# schematics.net
KiCad netlist of a schematic drawn in EasyEDA
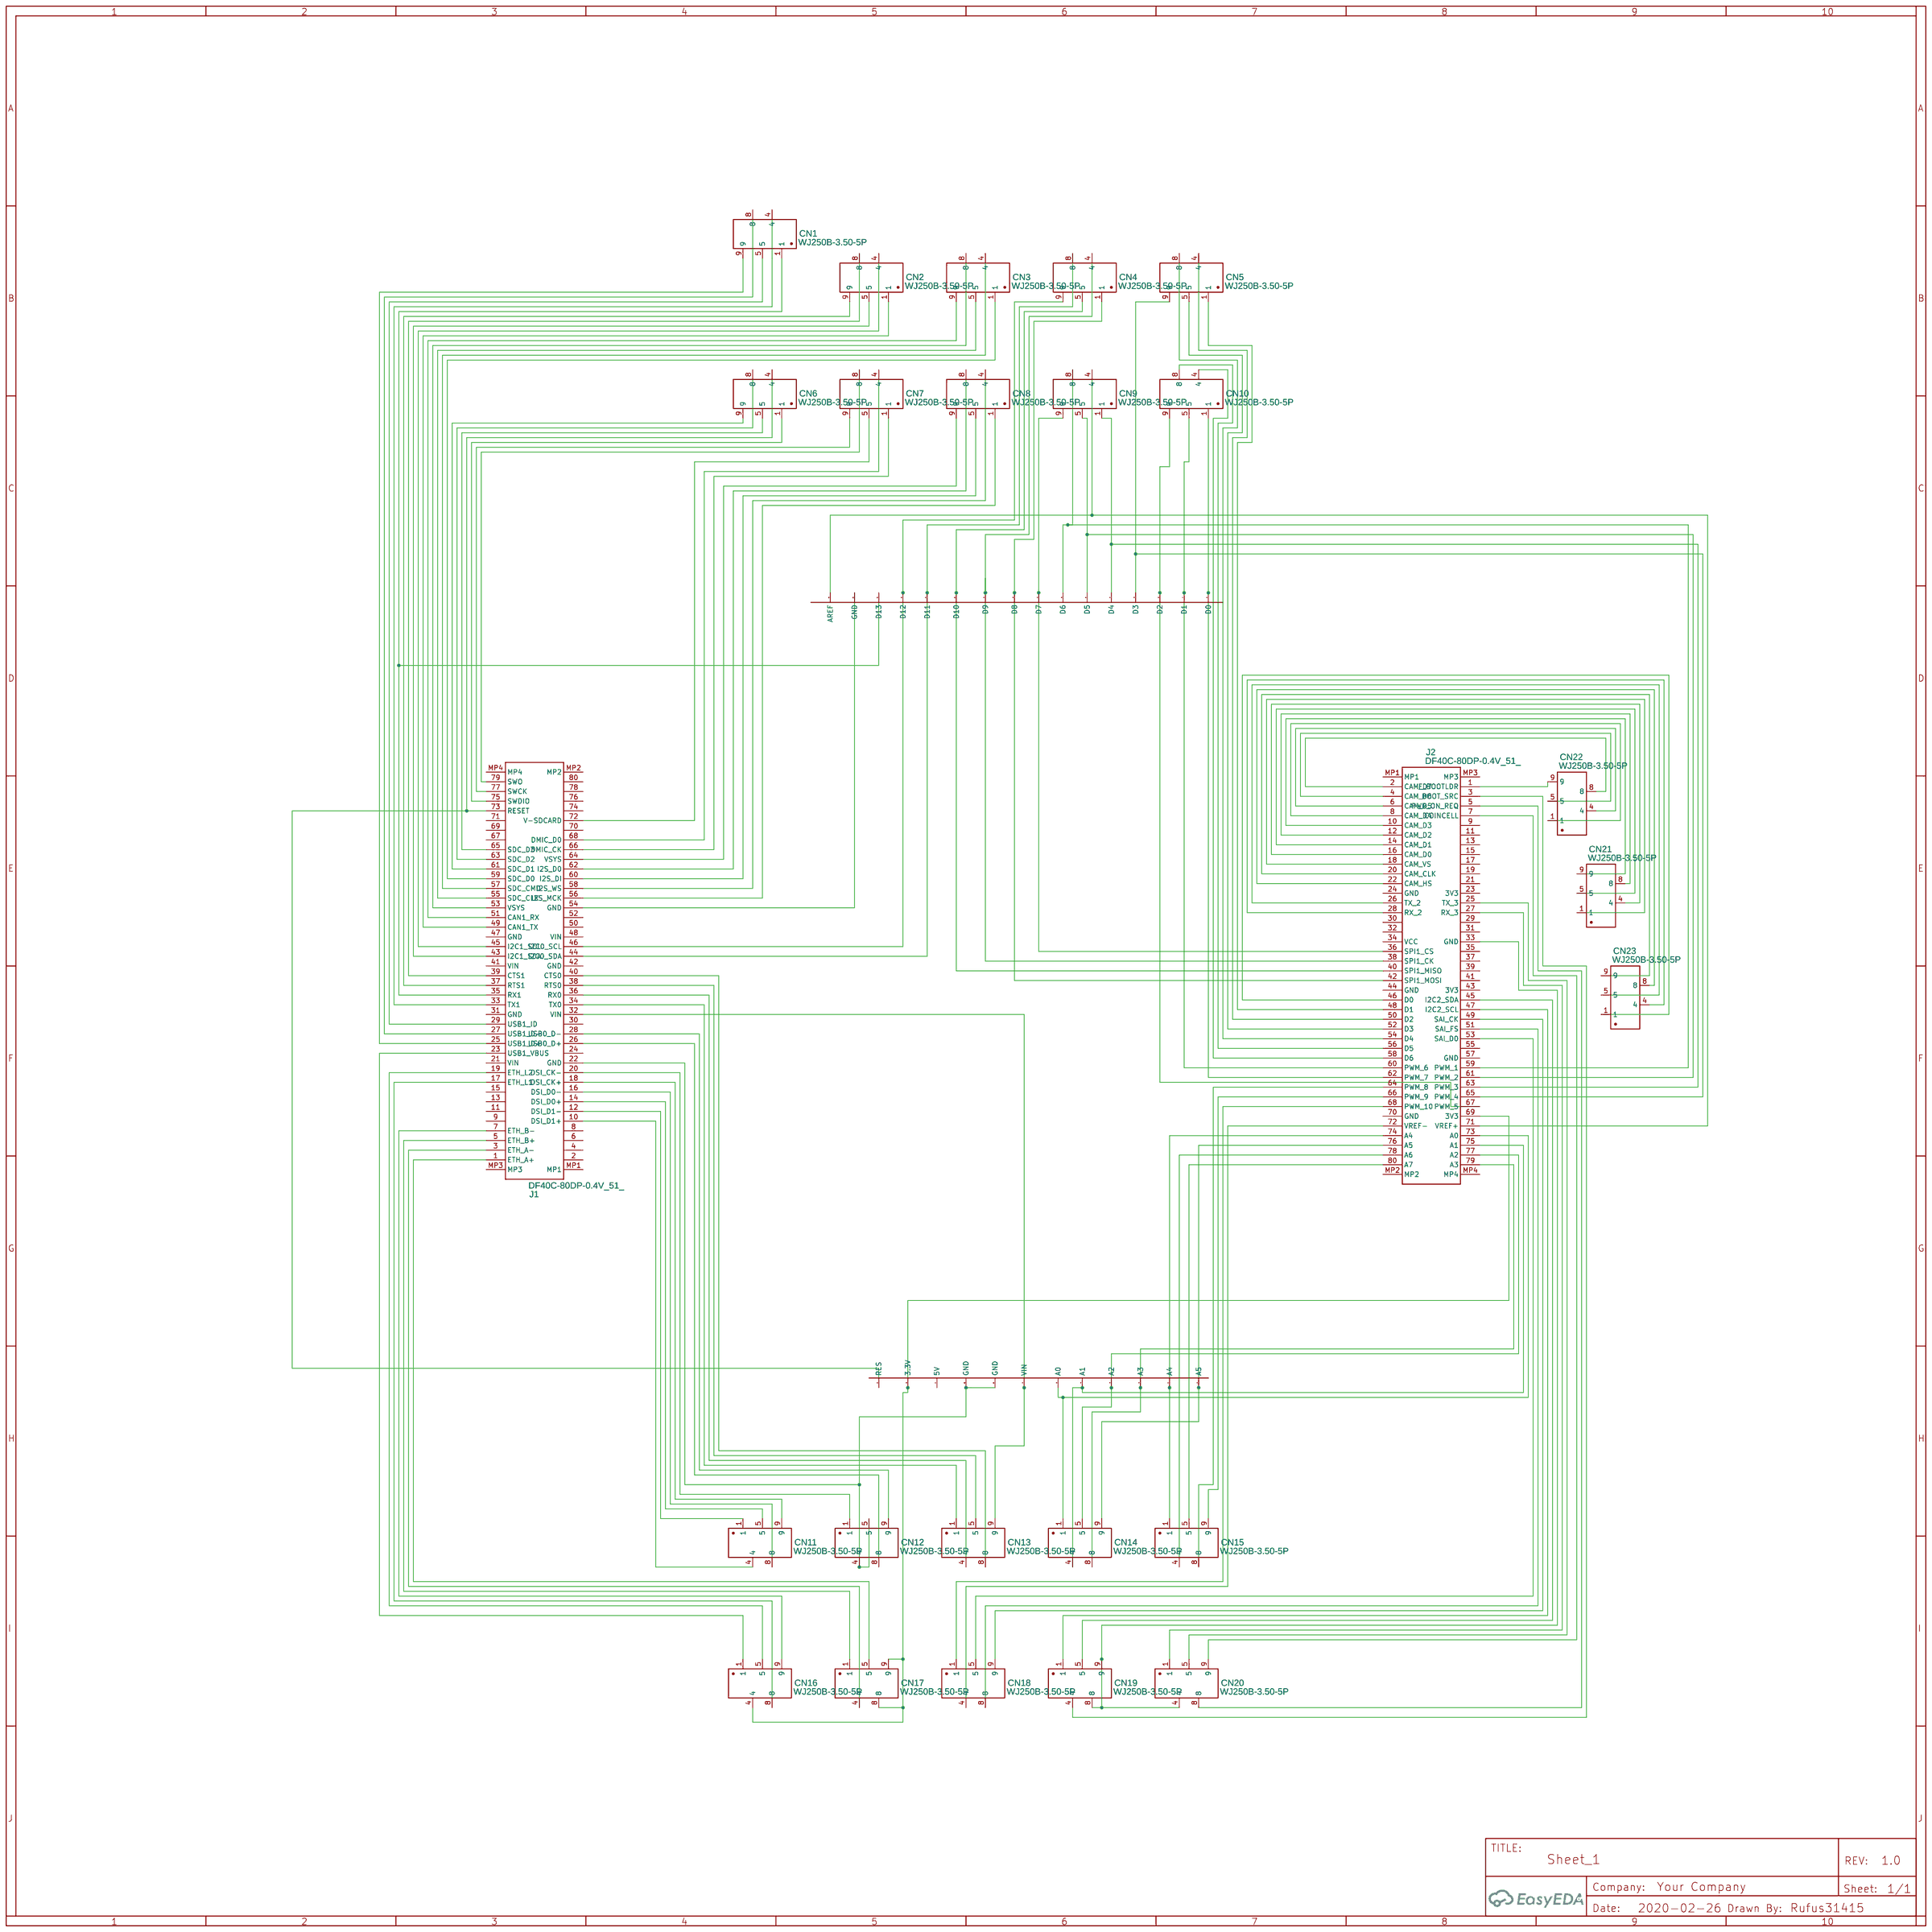
[diagram p0: schematic sheet]

(export (version "E")
  (design (tool "Eeschema 10.0.6"))
  (components
    (comp (ref "CN1")
      (value "WJ250B-3.50-5P")
      (fields (field (name "BOM_Supplier Part") "C8453"))
      (libsource (lib "") (part "WJ250B-3.50-5P_1"))
    )
    (comp (ref "CN2")
      (value "WJ250B-3.50-5P")
      (fields (field (name "BOM_Supplier Part") "C8453"))
      (libsource (lib "") (part "WJ250B-3.50-5P_1"))
    )
    (comp (ref "CN3")
      (value "WJ250B-3.50-5P")
      (fields (field (name "BOM_Supplier Part") "C8453"))
      (libsource (lib "") (part "WJ250B-3.50-5P_1"))
    )
    (comp (ref "CN4")
      (value "WJ250B-3.50-5P")
      (fields (field (name "BOM_Supplier Part") "C8453"))
      (libsource (lib "") (part "WJ250B-3.50-5P_1"))
    )
    (comp (ref "CN5")
      (value "WJ250B-3.50-5P")
      (fields (field (name "BOM_Supplier Part") "C8453"))
      (libsource (lib "") (part "WJ250B-3.50-5P_1"))
    )
    (comp (ref "CN6")
      (value "WJ250B-3.50-5P")
      (fields (field (name "BOM_Supplier Part") "C8453"))
      (libsource (lib "") (part "WJ250B-3.50-5P_1"))
    )
    (comp (ref "CN7")
      (value "WJ250B-3.50-5P")
      (fields (field (name "BOM_Supplier Part") "C8453"))
      (libsource (lib "") (part "WJ250B-3.50-5P_1"))
    )
    (comp (ref "CN8")
      (value "WJ250B-3.50-5P")
      (fields (field (name "BOM_Supplier Part") "C8453"))
      (libsource (lib "") (part "WJ250B-3.50-5P_1"))
    )
    (comp (ref "CN9")
      (value "WJ250B-3.50-5P")
      (fields (field (name "BOM_Supplier Part") "C8453"))
      (libsource (lib "") (part "WJ250B-3.50-5P_1"))
    )
    (comp (ref "CN10")
      (value "WJ250B-3.50-5P")
      (fields (field (name "BOM_Supplier Part") "C8453"))
      (libsource (lib "") (part "WJ250B-3.50-5P_1"))
    )
    (comp (ref "CN11")
      (value "WJ250B-3.50-5P")
      (fields (field (name "BOM_Supplier Part") "C8453"))
      (libsource (lib "") (part "WJ250B-3.50-5P"))
    )
    (comp (ref "CN12")
      (value "WJ250B-3.50-5P")
      (fields (field (name "BOM_Supplier Part") "C8453"))
      (libsource (lib "") (part "WJ250B-3.50-5P"))
    )
    (comp (ref "CN13")
      (value "WJ250B-3.50-5P")
      (fields (field (name "BOM_Supplier Part") "C8453"))
      (libsource (lib "") (part "WJ250B-3.50-5P"))
    )
    (comp (ref "CN14")
      (value "WJ250B-3.50-5P")
      (fields (field (name "BOM_Supplier Part") "C8453"))
      (libsource (lib "") (part "WJ250B-3.50-5P"))
    )
    (comp (ref "CN15")
      (value "WJ250B-3.50-5P")
      (fields (field (name "BOM_Supplier Part") "C8453"))
      (libsource (lib "") (part "WJ250B-3.50-5P"))
    )
    (comp (ref "CN16")
      (value "WJ250B-3.50-5P")
      (fields (field (name "BOM_Supplier Part") "C8453"))
      (libsource (lib "") (part "WJ250B-3.50-5P"))
    )
    (comp (ref "CN17")
      (value "WJ250B-3.50-5P")
      (fields (field (name "BOM_Supplier Part") "C8453"))
      (libsource (lib "") (part "WJ250B-3.50-5P"))
    )
    (comp (ref "CN18")
      (value "WJ250B-3.50-5P")
      (fields (field (name "BOM_Supplier Part") "C8453"))
      (libsource (lib "") (part "WJ250B-3.50-5P"))
    )
    (comp (ref "CN19")
      (value "WJ250B-3.50-5P")
      (fields (field (name "BOM_Supplier Part") "C8453"))
      (libsource (lib "") (part "WJ250B-3.50-5P"))
    )
    (comp (ref "CN20")
      (value "WJ250B-3.50-5P")
      (fields (field (name "BOM_Supplier Part") "C8453"))
      (libsource (lib "") (part "WJ250B-3.50-5P"))
    )
    (comp (ref "CN21")
      (value "WJ250B-3.50-5P")
      (fields (field (name "BOM_Supplier Part") "C8453"))
      (libsource (lib "") (part "WJ250B-3.50-5P_2"))
    )
    (comp (ref "CN22")
      (value "WJ250B-3.50-5P")
      (fields (field (name "BOM_Supplier Part") "C8453"))
      (libsource (lib "") (part "WJ250B-3.50-5P_2"))
    )
    (comp (ref "CN23")
      (value "WJ250B-3.50-5P")
      (fields (field (name "BOM_Supplier Part") "C8453"))
      (libsource (lib "") (part "WJ250B-3.50-5P_2"))
    )
    (comp (ref "J1") (value "DF40C-80DP-0.4V_51_") (libsource (lib "") (part "DF40C-80DP-0.4V_51_")))
    (comp (ref "J2") (value "DF40C-80DP-0.4V_51_") (libsource (lib "") (part "DF40C-80DP-0.4V_51__1")))
    (comp (ref "U1")
      (value "ARDUINO_SHIELDNO_SILK BIG")
      (libsource (lib "") (part "ARDUINO_SHIELDNO_SILK BIG"))
    )
  )
  (nets
    (net (code "1") (name "Net-(CN3-Pad8)") (class "Default")
      (node (ref "CN3") (pin "8") (pinfunction "8_8") (pintype "unspecified"))
      (node (ref "J1") (pin "53") (pinfunction "VSYS_53") (pintype "bidirectional"))
    )
    (net (code "2") (name "Net-(CN8-Pad9)") (class "Default")
      (node (ref "CN8") (pin "9") (pinfunction "9_9") (pintype "unspecified"))
      (node (ref "J1") (pin "64") (pinfunction "VSYS_64") (pintype "bidirectional"))
    )
    (net (code "3") (name "Net-(CN12-Pad4)") (class "Default")
      (node (ref "CN12") (pin "4") (pinfunction "4_4") (pintype "unspecified"))
      (node (ref "CN12") (pin "5") (pinfunction "5_5") (pintype "unspecified"))
      (node (ref "J1") (pin "22") (pinfunction "GND_22") (pintype "bidirectional"))
      (node (ref "U1") (pin "GND@0") (pinfunction "GND_GND@0") (pintype "unspecified"))
      (node (ref "U1") (pin "GND@1") (pinfunction "GND_GND@1") (pintype "unspecified"))
    )
    (net (code "4") (name "Net-(CN13-Pad9)") (class "Default")
      (node (ref "CN13") (pin "9") (pinfunction "9_9") (pintype "unspecified"))
      (node (ref "J1") (pin "32") (pinfunction "VIN_32") (pintype "bidirectional"))
      (node (ref "U1") (pin "VIN") (pinfunction "VIN_VIN") (pintype "unspecified"))
    )
    (net (code "5") (name "Net-(CN16-Pad4)") (class "Default")
      (node (ref "CN16") (pin "4") (pinfunction "4_4") (pintype "unspecified"))
      (node (ref "CN17") (pin "8") (pinfunction "8_8") (pintype "unspecified"))
      (node (ref "CN17") (pin "9") (pinfunction "9_9") (pintype "unspecified"))
      (node (ref "J2") (pin "69") (pinfunction "3V3_69") (pintype "bidirectional"))
      (node (ref "U1") (pin "3.3V") (pinfunction "3.3V_3.3V") (pintype "unspecified"))
    )
    (net (code "6") (name "Net-(CN19-Pad8)") (class "Default")
      (node (ref "CN19") (pin "8") (pinfunction "8_8") (pintype "unspecified"))
      (node (ref "CN19") (pin "9") (pinfunction "9_9") (pintype "unspecified"))
      (node (ref "CN20") (pin "4") (pinfunction "4_4") (pintype "unspecified"))
      (node (ref "J2") (pin "33") (pinfunction "GND_33") (pintype "bidirectional"))
    )
    (net (code "7") (name "Net-(J1-CAN1_RX)") (class "Default")
      (node (ref "CN3") (pin "9") (pinfunction "9_9") (pintype "unspecified"))
      (node (ref "J1") (pin "51") (pinfunction "CAN1_RX_51") (pintype "bidirectional"))
    )
    (net (code "8") (name "Net-(J1-CAN1_TX)") (class "Default")
      (node (ref "CN2") (pin "1") (pinfunction "1_1") (pintype "unspecified"))
      (node (ref "J1") (pin "49") (pinfunction "CAN1_TX_49") (pintype "bidirectional"))
    )
    (net (code "9") (name "Net-(J1-CTS0)") (class "Default")
      (node (ref "CN13") (pin "8") (pinfunction "8_8") (pintype "unspecified"))
      (node (ref "J1") (pin "40") (pinfunction "CTS0_40") (pintype "bidirectional"))
    )
    (net (code "10") (name "Net-(J1-CTS1)") (class "Default")
      (node (ref "CN2") (pin "8") (pinfunction "8_8") (pintype "unspecified"))
      (node (ref "J1") (pin "39") (pinfunction "CTS1_39") (pintype "bidirectional"))
    )
    (net (code "11") (name "Net-(J1-DMIC_CK)") (class "Default")
      (node (ref "CN7") (pin "1") (pinfunction "1_1") (pintype "unspecified"))
      (node (ref "J1") (pin "66") (pinfunction "DMIC_CK_66") (pintype "bidirectional"))
    )
    (net (code "12") (name "Net-(J1-DMIC_D0)") (class "Default")
      (node (ref "CN7") (pin "4") (pinfunction "4_4") (pintype "unspecified"))
      (node (ref "J1") (pin "68") (pinfunction "DMIC_D0_68") (pintype "bidirectional"))
    )
    (net (code "13") (name "Net-(J1-DSI_CK+)") (class "Default")
      (node (ref "CN11") (pin "9") (pinfunction "9_9") (pintype "unspecified"))
      (node (ref "J1") (pin "18") (pinfunction "DSI_CK+_18") (pintype "bidirectional"))
    )
    (net (code "14") (name "Net-(J1-DSI_CK-)") (class "Default")
      (node (ref "CN12") (pin "1") (pinfunction "1_1") (pintype "unspecified"))
      (node (ref "J1") (pin "20") (pinfunction "DSI_CK-_20") (pintype "bidirectional"))
    )
    (net (code "15") (name "Net-(J1-DSI_D0+)") (class "Default")
      (node (ref "CN11") (pin "5") (pinfunction "5_5") (pintype "unspecified"))
      (node (ref "J1") (pin "14") (pinfunction "DSI_D0+_14") (pintype "bidirectional"))
    )
    (net (code "16") (name "Net-(J1-DSI_D0-)") (class "Default")
      (node (ref "CN11") (pin "8") (pinfunction "8_8") (pintype "unspecified"))
      (node (ref "J1") (pin "16") (pinfunction "DSI_D0-_16") (pintype "bidirectional"))
    )
    (net (code "17") (name "Net-(J1-DSI_D1+)") (class "Default")
      (node (ref "CN11") (pin "4") (pinfunction "4_4") (pintype "unspecified"))
      (node (ref "J1") (pin "10") (pinfunction "DSI_D1+_10") (pintype "bidirectional"))
    )
    (net (code "18") (name "Net-(J1-DSI_D1-)") (class "Default")
      (node (ref "CN11") (pin "1") (pinfunction "1_1") (pintype "unspecified"))
      (node (ref "J1") (pin "12") (pinfunction "DSI_D1-_12") (pintype "bidirectional"))
    )
    (net (code "19") (name "Net-(J1-ETH_A+)") (class "Default")
      (node (ref "CN17") (pin "5") (pinfunction "5_5") (pintype "unspecified"))
      (node (ref "J1") (pin "1") (pinfunction "ETH_A+_1") (pintype "bidirectional"))
    )
    (net (code "20") (name "Net-(J1-ETH_A-)") (class "Default")
      (node (ref "CN17") (pin "4") (pinfunction "4_4") (pintype "unspecified"))
      (node (ref "J1") (pin "3") (pinfunction "ETH_A-_3") (pintype "bidirectional"))
    )
    (net (code "21") (name "Net-(J1-ETH_B+)") (class "Default")
      (node (ref "CN17") (pin "1") (pinfunction "1_1") (pintype "unspecified"))
      (node (ref "J1") (pin "5") (pinfunction "ETH_B+_5") (pintype "bidirectional"))
    )
    (net (code "22") (name "Net-(J1-ETH_B-)") (class "Default")
      (node (ref "CN16") (pin "9") (pinfunction "9_9") (pintype "unspecified"))
      (node (ref "J1") (pin "7") (pinfunction "ETH_B-_7") (pintype "bidirectional"))
    )
    (net (code "23") (name "Net-(J1-ETH_L1)") (class "Default")
      (node (ref "CN16") (pin "8") (pinfunction "8_8") (pintype "unspecified"))
      (node (ref "J1") (pin "17") (pinfunction "ETH_L1_17") (pintype "bidirectional"))
    )
    (net (code "24") (name "Net-(J1-ETH_L2)") (class "Default")
      (node (ref "CN16") (pin "5") (pinfunction "5_5") (pintype "unspecified"))
      (node (ref "J1") (pin "19") (pinfunction "ETH_L2_19") (pintype "bidirectional"))
    )
    (net (code "25") (name "Net-(J1-GND-Pad54)") (class "Default")
      (node (ref "J1") (pin "54") (pinfunction "GND_54") (pintype "bidirectional"))
      (node (ref "U1") (pin "GND@2") (pinfunction "GND_GND@2") (pintype "unspecified"))
    )
    (net (code "26") (name "Net-(J1-I2C0_SCL)") (class "Default")
      (node (ref "CN4") (pin "9") (pinfunction "9_9") (pintype "unspecified"))
      (node (ref "J1") (pin "46") (pinfunction "I2C0_SCL_46") (pintype "bidirectional"))
      (node (ref "U1") (pin "D12") (pinfunction "D12_D12") (pintype "unspecified"))
    )
    (net (code "27") (name "Net-(J1-I2C0_SDA)") (class "Default")
      (node (ref "CN4") (pin "8") (pinfunction "8_8") (pintype "unspecified"))
      (node (ref "J1") (pin "44") (pinfunction "I2C0_SDA_44") (pintype "bidirectional"))
      (node (ref "U1") (pin "D11") (pinfunction "D11_D11") (pintype "unspecified"))
    )
    (net (code "28") (name "Net-(J1-I2C1_SCL)") (class "Default")
      (node (ref "CN2") (pin "4") (pinfunction "4_4") (pintype "unspecified"))
      (node (ref "J1") (pin "45") (pinfunction "I2C1_SCL_45") (pintype "bidirectional"))
    )
    (net (code "29") (name "Net-(J1-I2C1_SDA)") (class "Default")
      (node (ref "CN2") (pin "5") (pinfunction "5_5") (pintype "unspecified"))
      (node (ref "J1") (pin "43") (pinfunction "I2C1_SDA_43") (pintype "bidirectional"))
    )
    (net (code "30") (name "Net-(J1-I2S_D0)") (class "Default")
      (node (ref "CN8") (pin "8") (pinfunction "8_8") (pintype "unspecified"))
      (node (ref "J1") (pin "62") (pinfunction "I2S_D0_62") (pintype "bidirectional"))
    )
    (net (code "31") (name "Net-(J1-I2S_DI)") (class "Default")
      (node (ref "CN8") (pin "5") (pinfunction "5_5") (pintype "unspecified"))
      (node (ref "J1") (pin "60") (pinfunction "I2S_DI_60") (pintype "bidirectional"))
    )
    (net (code "32") (name "Net-(J1-I2S_MCK)") (class "Default")
      (node (ref "CN8") (pin "1") (pinfunction "1_1") (pintype "unspecified"))
      (node (ref "J1") (pin "56") (pinfunction "I2S_MCK_56") (pintype "bidirectional"))
    )
    (net (code "33") (name "Net-(J1-I2S_WS)") (class "Default")
      (node (ref "CN8") (pin "4") (pinfunction "4_4") (pintype "unspecified"))
      (node (ref "J1") (pin "58") (pinfunction "I2S_WS_58") (pintype "bidirectional"))
    )
    (net (code "34") (name "Net-(J1-RESET)") (class "Default")
      (node (ref "CN6") (pin "4") (pinfunction "4_4") (pintype "unspecified"))
      (node (ref "J1") (pin "73") (pinfunction "RESET_73") (pintype "bidirectional"))
      (node (ref "U1") (pin "RES") (pinfunction "RES_RES") (pintype "unspecified"))
    )
    (net (code "35") (name "Net-(J1-RTS0)") (class "Default")
      (node (ref "CN13") (pin "5") (pinfunction "5_5") (pintype "unspecified"))
      (node (ref "J1") (pin "38") (pinfunction "RTS0_38") (pintype "bidirectional"))
    )
    (net (code "36") (name "Net-(J1-RTS1)") (class "Default")
      (node (ref "CN2") (pin "9") (pinfunction "9_9") (pintype "unspecified"))
      (node (ref "J1") (pin "37") (pinfunction "RTS1_37") (pintype "bidirectional"))
    )
    (net (code "37") (name "Net-(J1-RX0)") (class "Default")
      (node (ref "CN13") (pin "4") (pinfunction "4_4") (pintype "unspecified"))
      (node (ref "J1") (pin "36") (pinfunction "RX0_36") (pintype "bidirectional"))
    )
    (net (code "38") (name "Net-(J1-RX1)") (class "Default")
      (node (ref "CN1") (pin "1") (pinfunction "1_1") (pintype "unspecified"))
      (node (ref "J1") (pin "35") (pinfunction "RX1_35") (pintype "bidirectional"))
      (node (ref "U1") (pin "D13") (pinfunction "D13_D13") (pintype "unspecified"))
    )
    (net (code "39") (name "Net-(J1-SDC_CLK)") (class "Default")
      (node (ref "CN3") (pin "5") (pinfunction "5_5") (pintype "unspecified"))
      (node (ref "J1") (pin "55") (pinfunction "SDC_CLK_55") (pintype "bidirectional"))
    )
    (net (code "40") (name "Net-(J1-SDC_CMD)") (class "Default")
      (node (ref "CN3") (pin "4") (pinfunction "4_4") (pintype "unspecified"))
      (node (ref "J1") (pin "57") (pinfunction "SDC_CMD_57") (pintype "bidirectional"))
    )
    (net (code "41") (name "Net-(J1-SDC_D0)") (class "Default")
      (node (ref "CN3") (pin "1") (pinfunction "1_1") (pintype "unspecified"))
      (node (ref "J1") (pin "59") (pinfunction "SDC_D0_59") (pintype "bidirectional"))
    )
    (net (code "42") (name "Net-(J1-SDC_D1)") (class "Default")
      (node (ref "CN6") (pin "9") (pinfunction "9_9") (pintype "unspecified"))
      (node (ref "J1") (pin "61") (pinfunction "SDC_D1_61") (pintype "bidirectional"))
    )
    (net (code "43") (name "Net-(J1-SDC_D2)") (class "Default")
      (node (ref "CN6") (pin "8") (pinfunction "8_8") (pintype "unspecified"))
      (node (ref "J1") (pin "63") (pinfunction "SDC_D2_63") (pintype "bidirectional"))
    )
    (net (code "44") (name "Net-(J1-SDC_D3)") (class "Default")
      (node (ref "CN6") (pin "5") (pinfunction "5_5") (pintype "unspecified"))
      (node (ref "J1") (pin "65") (pinfunction "SDC_D3_65") (pintype "bidirectional"))
    )
    (net (code "45") (name "Net-(J1-SWCK)") (class "Default")
      (node (ref "CN7") (pin "9") (pinfunction "9_9") (pintype "unspecified"))
      (node (ref "J1") (pin "77") (pinfunction "SWCK_77") (pintype "bidirectional"))
    )
    (net (code "46") (name "Net-(J1-SWDIO)") (class "Default")
      (node (ref "CN6") (pin "1") (pinfunction "1_1") (pintype "unspecified"))
      (node (ref "J1") (pin "75") (pinfunction "SWDIO_75") (pintype "bidirectional"))
    )
    (net (code "47") (name "Net-(J1-SWO)") (class "Default")
      (node (ref "CN7") (pin "8") (pinfunction "8_8") (pintype "unspecified"))
      (node (ref "J1") (pin "79") (pinfunction "SWO_79") (pintype "bidirectional"))
    )
    (net (code "48") (name "Net-(J1-TX0)") (class "Default")
      (node (ref "CN13") (pin "1") (pinfunction "1_1") (pintype "unspecified"))
      (node (ref "J1") (pin "34") (pinfunction "TX0_34") (pintype "bidirectional"))
    )
    (net (code "49") (name "Net-(J1-TX1)") (class "Default")
      (node (ref "CN1") (pin "4") (pinfunction "4_4") (pintype "unspecified"))
      (node (ref "J1") (pin "33") (pinfunction "TX1_33") (pintype "bidirectional"))
    )
    (net (code "50") (name "Net-(J1-USB0_D+)") (class "Default")
      (node (ref "CN12") (pin "8") (pinfunction "8_8") (pintype "unspecified"))
      (node (ref "J1") (pin "26") (pinfunction "USB0_D+_26") (pintype "bidirectional"))
    )
    (net (code "51") (name "Net-(J1-USB0_D-)") (class "Default")
      (node (ref "CN12") (pin "9") (pinfunction "9_9") (pintype "unspecified"))
      (node (ref "J1") (pin "28") (pinfunction "USB0_D-_28") (pintype "bidirectional"))
    )
    (net (code "52") (name "Net-(J1-USB1_D+)") (class "Default")
      (node (ref "CN1") (pin "9") (pinfunction "9_9") (pintype "unspecified"))
      (node (ref "J1") (pin "25") (pinfunction "USB1_D+_25") (pintype "bidirectional"))
    )
    (net (code "53") (name "Net-(J1-USB1_D-)") (class "Default")
      (node (ref "CN1") (pin "8") (pinfunction "8_8") (pintype "unspecified"))
      (node (ref "J1") (pin "27") (pinfunction "USB1_D-_27") (pintype "bidirectional"))
    )
    (net (code "54") (name "Net-(J1-USB1_ID)") (class "Default")
      (node (ref "CN1") (pin "5") (pinfunction "5_5") (pintype "unspecified"))
      (node (ref "J1") (pin "29") (pinfunction "USB1_ID_29") (pintype "bidirectional"))
    )
    (net (code "55") (name "Net-(J1-USB1_VBUS)") (class "Default")
      (node (ref "CN16") (pin "1") (pinfunction "1_1") (pintype "unspecified"))
      (node (ref "J1") (pin "23") (pinfunction "USB1_VBUS_23") (pintype "bidirectional"))
    )
    (net (code "56") (name "Net-(J1-V-SDCARD)") (class "Default")
      (node (ref "CN7") (pin "5") (pinfunction "5_5") (pintype "unspecified"))
      (node (ref "J1") (pin "72") (pinfunction "V-SDCARD_72") (pintype "bidirectional"))
    )
    (net (code "57") (name "Net-(J2-A0)") (class "Default")
      (node (ref "CN14") (pin "1") (pinfunction "1_1") (pintype "unspecified"))
      (node (ref "J2") (pin "73") (pinfunction "A0_73") (pintype "bidirectional"))
      (node (ref "U1") (pin "A0") (pinfunction "A0_A0") (pintype "unspecified"))
    )
    (net (code "58") (name "Net-(J2-A1)") (class "Default")
      (node (ref "CN14") (pin "4") (pinfunction "4_4") (pintype "unspecified"))
      (node (ref "J2") (pin "75") (pinfunction "A1_75") (pintype "bidirectional"))
      (node (ref "U1") (pin "A1") (pinfunction "A1_A1") (pintype "unspecified"))
    )
    (net (code "59") (name "Net-(J2-A2)") (class "Default")
      (node (ref "CN14") (pin "5") (pinfunction "5_5") (pintype "unspecified"))
      (node (ref "J2") (pin "77") (pinfunction "A2_77") (pintype "bidirectional"))
      (node (ref "U1") (pin "A2") (pinfunction "A2_A2") (pintype "unspecified"))
    )
    (net (code "60") (name "Net-(J2-A3)") (class "Default")
      (node (ref "CN14") (pin "8") (pinfunction "8_8") (pintype "unspecified"))
      (node (ref "J2") (pin "79") (pinfunction "A3_79") (pintype "bidirectional"))
      (node (ref "U1") (pin "A3") (pinfunction "A3_A3") (pintype "unspecified"))
    )
    (net (code "61") (name "Net-(J2-A4)") (class "Default")
      (node (ref "CN14") (pin "9") (pinfunction "9_9") (pintype "unspecified"))
      (node (ref "CN15") (pin "1") (pinfunction "1_1") (pintype "unspecified"))
      (node (ref "J2") (pin "74") (pinfunction "A4_74") (pintype "bidirectional"))
      (node (ref "J2") (pin "76") (pinfunction "A5_76") (pintype "bidirectional"))
      (node (ref "U1") (pin "A4") (pinfunction "A4_A4") (pintype "unspecified"))
      (node (ref "U1") (pin "A5") (pinfunction "A5_A5") (pintype "unspecified"))
    )
    (net (code "62") (name "Net-(J2-A6)") (class "Default")
      (node (ref "CN15") (pin "4") (pinfunction "4_4") (pintype "unspecified"))
      (node (ref "J2") (pin "78") (pinfunction "A6_78") (pintype "bidirectional"))
    )
    (net (code "63") (name "Net-(J2-A7)") (class "Default")
      (node (ref "CN15") (pin "5") (pinfunction "5_5") (pintype "unspecified"))
      (node (ref "J2") (pin "80") (pinfunction "A7_80") (pintype "bidirectional"))
    )
    (net (code "64") (name "Net-(J2-BOOT_SRC)") (class "Default")
      (node (ref "CN19") (pin "4") (pinfunction "4_4") (pintype "unspecified"))
      (node (ref "J2") (pin "3") (pinfunction "BOOT_SRC_3") (pintype "bidirectional"))
    )
    (net (code "65") (name "Net-(J2-CAM_CLK)") (class "Default")
      (node (ref "CN23") (pin "9") (pinfunction "9_9") (pintype "unspecified"))
      (node (ref "J2") (pin "20") (pinfunction "CAM_CLK_20") (pintype "bidirectional"))
    )
    (net (code "66") (name "Net-(J2-CAM_D0)") (class "Default")
      (node (ref "CN21") (pin "4") (pinfunction "4_4") (pintype "unspecified"))
      (node (ref "J2") (pin "16") (pinfunction "CAM_D0_16") (pintype "bidirectional"))
    )
    (net (code "67") (name "Net-(J2-CAM_D1)") (class "Default")
      (node (ref "CN21") (pin "5") (pinfunction "5_5") (pintype "unspecified"))
      (node (ref "J2") (pin "14") (pinfunction "CAM_D1_14") (pintype "bidirectional"))
    )
    (net (code "68") (name "Net-(J2-CAM_D2)") (class "Default")
      (node (ref "CN21") (pin "8") (pinfunction "8_8") (pintype "unspecified"))
      (node (ref "J2") (pin "12") (pinfunction "CAM_D2_12") (pintype "bidirectional"))
    )
    (net (code "69") (name "Net-(J2-CAM_D3)") (class "Default")
      (node (ref "CN21") (pin "9") (pinfunction "9_9") (pintype "unspecified"))
      (node (ref "J2") (pin "10") (pinfunction "CAM_D3_10") (pintype "bidirectional"))
    )
    (net (code "70") (name "Net-(J2-CAM_D4)") (class "Default")
      (node (ref "CN22") (pin "1") (pinfunction "1_1") (pintype "unspecified"))
      (node (ref "J2") (pin "8") (pinfunction "CAM_D4_8") (pintype "bidirectional"))
    )
    (net (code "71") (name "Net-(J2-CAM_D5)") (class "Default")
      (node (ref "CN22") (pin "4") (pinfunction "4_4") (pintype "unspecified"))
      (node (ref "J2") (pin "6") (pinfunction "CAM_D5_6") (pintype "bidirectional"))
    )
    (net (code "72") (name "Net-(J2-CAM_D6)") (class "Default")
      (node (ref "CN22") (pin "5") (pinfunction "5_5") (pintype "unspecified"))
      (node (ref "J2") (pin "4") (pinfunction "CAM_D6_4") (pintype "bidirectional"))
    )
    (net (code "73") (name "Net-(J2-CAM_D7)") (class "Default")
      (node (ref "CN22") (pin "8") (pinfunction "8_8") (pintype "unspecified"))
      (node (ref "J2") (pin "2") (pinfunction "CAM_D7_2") (pintype "bidirectional"))
    )
    (net (code "74") (name "Net-(J2-CAM_HS)") (class "Default")
      (node (ref "CN23") (pin "8") (pinfunction "8_8") (pintype "unspecified"))
      (node (ref "J2") (pin "22") (pinfunction "CAM_HS_22") (pintype "bidirectional"))
    )
    (net (code "75") (name "Net-(J2-CAM_VS)") (class "Default")
      (node (ref "CN21") (pin "1") (pinfunction "1_1") (pintype "unspecified"))
      (node (ref "J2") (pin "18") (pinfunction "CAM_VS_18") (pintype "bidirectional"))
    )
    (net (code "76") (name "Net-(J2-COINCELL)") (class "Default")
      (node (ref "CN20") (pin "9") (pinfunction "9_9") (pintype "unspecified"))
      (node (ref "J2") (pin "7") (pinfunction "COINCELL_7") (pintype "bidirectional"))
    )
    (net (code "77") (name "Net-(J2-D0)") (class "Default")
      (node (ref "CN23") (pin "1") (pinfunction "1_1") (pintype "unspecified"))
      (node (ref "J2") (pin "46") (pinfunction "D0_46") (pintype "bidirectional"))
    )
    (net (code "78") (name "Net-(J2-D1)") (class "Default")
      (node (ref "CN5") (pin "1") (pinfunction "1_1") (pintype "unspecified"))
      (node (ref "J2") (pin "48") (pinfunction "D1_48") (pintype "bidirectional"))
    )
    (net (code "79") (name "Net-(J2-D2)") (class "Default")
      (node (ref "CN5") (pin "4") (pinfunction "4_4") (pintype "unspecified"))
      (node (ref "J2") (pin "50") (pinfunction "D2_50") (pintype "bidirectional"))
    )
    (net (code "80") (name "Net-(J2-D3)") (class "Default")
      (node (ref "CN5") (pin "5") (pinfunction "5_5") (pintype "unspecified"))
      (node (ref "J2") (pin "52") (pinfunction "D3_52") (pintype "bidirectional"))
    )
    (net (code "81") (name "Net-(J2-D4)") (class "Default")
      (node (ref "CN5") (pin "8") (pinfunction "8_8") (pintype "unspecified"))
      (node (ref "J2") (pin "54") (pinfunction "D4_54") (pintype "bidirectional"))
    )
    (net (code "82") (name "Net-(J2-D5)") (class "Default")
      (node (ref "CN10") (pin "8") (pinfunction "8_8") (pintype "unspecified"))
      (node (ref "J2") (pin "56") (pinfunction "D5_56") (pintype "bidirectional"))
    )
    (net (code "83") (name "Net-(J2-D6)") (class "Default")
      (node (ref "CN10") (pin "4") (pinfunction "4_4") (pintype "unspecified"))
      (node (ref "J2") (pin "58") (pinfunction "D6_58") (pintype "bidirectional"))
    )
    (net (code "84") (name "Net-(J2-F_BOOTLDR)") (class "Default")
      (node (ref "CN22") (pin "9") (pinfunction "9_9") (pintype "unspecified"))
      (node (ref "J2") (pin "1") (pinfunction "F_BOOTLDR_1") (pintype "bidirectional"))
    )
    (net (code "85") (name "Net-(J2-I2C2_SCL)") (class "Default")
      (node (ref "CN19") (pin "1") (pinfunction "1_1") (pintype "unspecified"))
      (node (ref "J2") (pin "47") (pinfunction "I2C2_SCL_47") (pintype "bidirectional"))
    )
    (net (code "86") (name "Net-(J2-I2C2_SDA)") (class "Default")
      (node (ref "CN19") (pin "5") (pinfunction "5_5") (pintype "unspecified"))
      (node (ref "J2") (pin "45") (pinfunction "I2C2_SDA_45") (pintype "bidirectional"))
    )
    (net (code "87") (name "Net-(J2-PWM_1)") (class "Default")
      (node (ref "CN9") (pin "8") (pinfunction "8_8") (pintype "unspecified"))
      (node (ref "J2") (pin "59") (pinfunction "PWM_1_59") (pintype "bidirectional"))
      (node (ref "U1") (pin "D6") (pinfunction "D6_D6") (pintype "unspecified"))
    )
    (net (code "88") (name "Net-(J2-PWM_2)") (class "Default")
      (node (ref "CN9") (pin "5") (pinfunction "5_5") (pintype "unspecified"))
      (node (ref "J2") (pin "61") (pinfunction "PWM_2_61") (pintype "bidirectional"))
      (node (ref "U1") (pin "D5") (pinfunction "D5_D5") (pintype "unspecified"))
    )
    (net (code "89") (name "Net-(J2-PWM_3)") (class "Default")
      (node (ref "CN9") (pin "1") (pinfunction "1_1") (pintype "unspecified"))
      (node (ref "J2") (pin "63") (pinfunction "PWM_3_63") (pintype "bidirectional"))
      (node (ref "U1") (pin "D4") (pinfunction "D4_D4") (pintype "unspecified"))
    )
    (net (code "90") (name "Net-(J2-PWM_4)") (class "Default")
      (node (ref "CN5") (pin "9") (pinfunction "9_9") (pintype "unspecified"))
      (node (ref "J2") (pin "65") (pinfunction "PWM_4_65") (pintype "bidirectional"))
      (node (ref "U1") (pin "D3") (pinfunction "D3_D3") (pintype "unspecified"))
    )
    (net (code "91") (name "Net-(J2-PWM_5)") (class "Default")
      (node (ref "CN10") (pin "9") (pinfunction "9_9") (pintype "unspecified"))
      (node (ref "J2") (pin "67") (pinfunction "PWM_5_67") (pintype "bidirectional"))
      (node (ref "U1") (pin "D2") (pinfunction "D2_D2") (pintype "unspecified"))
    )
    (net (code "92") (name "Net-(J2-PWM_6)") (class "Default")
      (node (ref "CN10") (pin "5") (pinfunction "5_5") (pintype "unspecified"))
      (node (ref "J2") (pin "60") (pinfunction "PWM_6_60") (pintype "bidirectional"))
      (node (ref "U1") (pin "TX") (pinfunction "D1_TX") (pintype "unspecified"))
    )
    (net (code "93") (name "Net-(J2-PWM_7)") (class "Default")
      (node (ref "CN10") (pin "1") (pinfunction "1_1") (pintype "unspecified"))
      (node (ref "J2") (pin "62") (pinfunction "PWM_7_62") (pintype "bidirectional"))
      (node (ref "U1") (pin "RX") (pinfunction "D0_RX") (pintype "unspecified"))
    )
    (net (code "94") (name "Net-(J2-PWM_8)") (class "Default")
      (node (ref "CN15") (pin "8") (pinfunction "8_8") (pintype "unspecified"))
      (node (ref "J2") (pin "64") (pinfunction "PWM_8_64") (pintype "bidirectional"))
    )
    (net (code "95") (name "Net-(J2-PWM_9)") (class "Default")
      (node (ref "CN15") (pin "9") (pinfunction "9_9") (pintype "unspecified"))
      (node (ref "J2") (pin "66") (pinfunction "PWM_9_66") (pintype "bidirectional"))
    )
    (net (code "96") (name "Net-(J2-PWM_10)") (class "Default")
      (node (ref "CN18") (pin "1") (pinfunction "1_1") (pintype "unspecified"))
      (node (ref "J2") (pin "68") (pinfunction "PWM_10_68") (pintype "bidirectional"))
    )
    (net (code "97") (name "Net-(J2-PWR_ON_REQ)") (class "Default")
      (node (ref "CN20") (pin "8") (pinfunction "8_8") (pintype "unspecified"))
      (node (ref "J2") (pin "5") (pinfunction "PWR_ON_REQ_5") (pintype "bidirectional"))
    )
    (net (code "98") (name "Net-(J2-RX_2)") (class "Default")
      (node (ref "CN23") (pin "4") (pinfunction "4_4") (pintype "unspecified"))
      (node (ref "J2") (pin "28") (pinfunction "RX_2_28") (pintype "bidirectional"))
    )
    (net (code "99") (name "Net-(J2-RX_3)") (class "Default")
      (node (ref "CN20") (pin "1") (pinfunction "1_1") (pintype "unspecified"))
      (node (ref "J2") (pin "27") (pinfunction "RX_3_27") (pintype "bidirectional"))
    )
    (net (code "100") (name "Net-(J2-SAI_CK)") (class "Default")
      (node (ref "CN18") (pin "9") (pinfunction "9_9") (pintype "unspecified"))
      (node (ref "J2") (pin "49") (pinfunction "SAI_CK_49") (pintype "bidirectional"))
    )
    (net (code "101") (name "Net-(J2-SAI_D0)") (class "Default")
      (node (ref "CN18") (pin "5") (pinfunction "5_5") (pintype "unspecified"))
      (node (ref "J2") (pin "53") (pinfunction "SAI_D0_53") (pintype "bidirectional"))
    )
    (net (code "102") (name "Net-(J2-SAI_FS)") (class "Default")
      (node (ref "CN18") (pin "8") (pinfunction "8_8") (pintype "unspecified"))
      (node (ref "J2") (pin "51") (pinfunction "SAI_FS_51") (pintype "bidirectional"))
    )
    (net (code "103") (name "Net-(J2-SPI1_CK)") (class "Default")
      (node (ref "CN4") (pin "4") (pinfunction "4_4") (pintype "unspecified"))
      (node (ref "J2") (pin "38") (pinfunction "SPI1_CK_38") (pintype "bidirectional"))
      (node (ref "U1") (pin "D9") (pinfunction "D9_D9") (pintype "unspecified"))
    )
    (net (code "104") (name "Net-(J2-SPI1_CS)") (class "Default")
      (node (ref "CN9") (pin "9") (pinfunction "9_9") (pintype "unspecified"))
      (node (ref "J2") (pin "36") (pinfunction "SPI1_CS_36") (pintype "bidirectional"))
      (node (ref "U1") (pin "D7") (pinfunction "D7_D7") (pintype "unspecified"))
    )
    (net (code "105") (name "Net-(J2-SPI1_MISO)") (class "Default")
      (node (ref "CN4") (pin "5") (pinfunction "5_5") (pintype "unspecified"))
      (node (ref "J2") (pin "40") (pinfunction "SPI1_MISO_40") (pintype "bidirectional"))
      (node (ref "U1") (pin "D10") (pinfunction "D10_D10") (pintype "unspecified"))
    )
    (net (code "106") (name "Net-(J2-SPI1_MOSI)") (class "Default")
      (node (ref "CN4") (pin "1") (pinfunction "1_1") (pintype "unspecified"))
      (node (ref "J2") (pin "42") (pinfunction "SPI1_MOSI_42") (pintype "bidirectional"))
      (node (ref "U1") (pin "D8") (pinfunction "D8_D8") (pintype "unspecified"))
    )
    (net (code "107") (name "Net-(J2-TX_2)") (class "Default")
      (node (ref "CN23") (pin "5") (pinfunction "5_5") (pintype "unspecified"))
      (node (ref "J2") (pin "26") (pinfunction "TX_2_26") (pintype "bidirectional"))
    )
    (net (code "108") (name "Net-(J2-TX_3)") (class "Default")
      (node (ref "CN20") (pin "5") (pinfunction "5_5") (pintype "unspecified"))
      (node (ref "J2") (pin "25") (pinfunction "TX_3_25") (pintype "bidirectional"))
    )
    (net (code "109") (name "Net-(J2-VREF+)") (class "Default")
      (node (ref "CN9") (pin "4") (pinfunction "4_4") (pintype "unspecified"))
      (node (ref "J2") (pin "71") (pinfunction "VREF+_71") (pintype "bidirectional"))
      (node (ref "U1") (pin "AREF") (pinfunction "AREF_AREF") (pintype "unspecified"))
    )
    (net (code "110") (name "Net-(J2-VREF-)") (class "Default")
      (node (ref "CN18") (pin "4") (pinfunction "4_4") (pintype "unspecified"))
      (node (ref "J2") (pin "72") (pinfunction "VREF-_72") (pintype "bidirectional"))
    )
    (net (code "111") (name "unconnected-(J1-GND-Pad31)") (class "Default")
      (node (ref "J1") (pin "31") (pinfunction "GND_31") (pintype "bidirectional"))
    )
    (net (code "112") (name "unconnected-(J1-GND-Pad42)") (class "Default")
      (node (ref "J1") (pin "42") (pinfunction "GND_42") (pintype "bidirectional"))
    )
    (net (code "113") (name "unconnected-(J1-GND-Pad47)") (class "Default")
      (node (ref "J1") (pin "47") (pinfunction "GND_47") (pintype "bidirectional"))
    )
    (net (code "114") (name "unconnected-(J1-Pad2)") (class "Default")
      (node (ref "J1") (pin "2") (pintype "bidirectional"))
    )
    (net (code "115") (name "unconnected-(J1-Pad4)") (class "Default")
      (node (ref "J1") (pin "4") (pintype "bidirectional"))
    )
    (net (code "116") (name "unconnected-(J1-Pad6)") (class "Default")
      (node (ref "J1") (pin "6") (pintype "bidirectional"))
    )
    (net (code "117") (name "unconnected-(J1-Pad8)") (class "Default")
      (node (ref "J1") (pin "8") (pintype "bidirectional"))
    )
    (net (code "118") (name "unconnected-(J1-Pad9)") (class "Default")
      (node (ref "J1") (pin "9") (pintype "bidirectional"))
    )
    (net (code "119") (name "unconnected-(J1-Pad11)") (class "Default")
      (node (ref "J1") (pin "11") (pintype "bidirectional"))
    )
    (net (code "120") (name "unconnected-(J1-Pad13)") (class "Default")
      (node (ref "J1") (pin "13") (pintype "bidirectional"))
    )
    (net (code "121") (name "unconnected-(J1-Pad15)") (class "Default")
      (node (ref "J1") (pin "15") (pintype "bidirectional"))
    )
    (net (code "122") (name "unconnected-(J1-Pad24)") (class "Default")
      (node (ref "J1") (pin "24") (pintype "bidirectional"))
    )
    (net (code "123") (name "unconnected-(J1-Pad30)") (class "Default")
      (node (ref "J1") (pin "30") (pintype "bidirectional"))
    )
    (net (code "124") (name "unconnected-(J1-Pad50)") (class "Default")
      (node (ref "J1") (pin "50") (pintype "bidirectional"))
    )
    (net (code "125") (name "unconnected-(J1-Pad52)") (class "Default")
      (node (ref "J1") (pin "52") (pintype "bidirectional"))
    )
    (net (code "126") (name "unconnected-(J1-Pad67)") (class "Default")
      (node (ref "J1") (pin "67") (pintype "bidirectional"))
    )
    (net (code "127") (name "unconnected-(J1-Pad69)") (class "Default")
      (node (ref "J1") (pin "69") (pintype "bidirectional"))
    )
    (net (code "128") (name "unconnected-(J1-Pad70)") (class "Default")
      (node (ref "J1") (pin "70") (pintype "bidirectional"))
    )
    (net (code "129") (name "unconnected-(J1-Pad71)") (class "Default")
      (node (ref "J1") (pin "71") (pintype "bidirectional"))
    )
    (net (code "130") (name "unconnected-(J1-Pad74)") (class "Default")
      (node (ref "J1") (pin "74") (pintype "bidirectional"))
    )
    (net (code "131") (name "unconnected-(J1-Pad76)") (class "Default")
      (node (ref "J1") (pin "76") (pintype "bidirectional"))
    )
    (net (code "132") (name "unconnected-(J1-Pad78)") (class "Default")
      (node (ref "J1") (pin "78") (pintype "bidirectional"))
    )
    (net (code "133") (name "unconnected-(J1-Pad80)") (class "Default")
      (node (ref "J1") (pin "80") (pintype "bidirectional"))
    )
    (net (code "134") (name "unconnected-(J1-PadMP1)") (class "Default")
      (node (ref "J1") (pin "MP1") (pinfunction "MP1_MP1") (pintype "bidirectional"))
    )
    (net (code "135") (name "unconnected-(J1-PadMP2)") (class "Default")
      (node (ref "J1") (pin "MP2") (pinfunction "MP2_MP2") (pintype "bidirectional"))
    )
    (net (code "136") (name "unconnected-(J1-PadMP3)") (class "Default")
      (node (ref "J1") (pin "MP3") (pinfunction "MP3_MP3") (pintype "bidirectional"))
    )
    (net (code "137") (name "unconnected-(J1-PadMP4)") (class "Default")
      (node (ref "J1") (pin "MP4") (pinfunction "MP4_MP4") (pintype "bidirectional"))
    )
    (net (code "138") (name "unconnected-(J1-VIN-Pad21)") (class "Default")
      (node (ref "J1") (pin "21") (pinfunction "VIN_21") (pintype "bidirectional"))
    )
    (net (code "139") (name "unconnected-(J1-VIN-Pad41)") (class "Default")
      (node (ref "J1") (pin "41") (pinfunction "VIN_41") (pintype "bidirectional"))
    )
    (net (code "140") (name "unconnected-(J1-VIN-Pad48)") (class "Default")
      (node (ref "J1") (pin "48") (pinfunction "VIN_48") (pintype "bidirectional"))
    )
    (net (code "141") (name "unconnected-(J2-3V3-Pad23)") (class "Default")
      (node (ref "J2") (pin "23") (pinfunction "3V3_23") (pintype "bidirectional"))
    )
    (net (code "142") (name "unconnected-(J2-3V3-Pad43)") (class "Default")
      (node (ref "J2") (pin "43") (pinfunction "3V3_43") (pintype "bidirectional"))
    )
    (net (code "143") (name "unconnected-(J2-GND-Pad24)") (class "Default")
      (node (ref "J2") (pin "24") (pinfunction "GND_24") (pintype "bidirectional"))
    )
    (net (code "144") (name "unconnected-(J2-GND-Pad44)") (class "Default")
      (node (ref "J2") (pin "44") (pinfunction "GND_44") (pintype "bidirectional"))
    )
    (net (code "145") (name "unconnected-(J2-GND-Pad57)") (class "Default")
      (node (ref "J2") (pin "57") (pinfunction "GND_57") (pintype "bidirectional"))
    )
    (net (code "146") (name "unconnected-(J2-GND-Pad70)") (class "Default")
      (node (ref "J2") (pin "70") (pinfunction "GND_70") (pintype "bidirectional"))
    )
    (net (code "147") (name "unconnected-(J2-Pad9)") (class "Default")
      (node (ref "J2") (pin "9") (pintype "bidirectional"))
    )
    (net (code "148") (name "unconnected-(J2-Pad11)") (class "Default")
      (node (ref "J2") (pin "11") (pintype "bidirectional"))
    )
    (net (code "149") (name "unconnected-(J2-Pad13)") (class "Default")
      (node (ref "J2") (pin "13") (pintype "bidirectional"))
    )
    (net (code "150") (name "unconnected-(J2-Pad15)") (class "Default")
      (node (ref "J2") (pin "15") (pintype "bidirectional"))
    )
    (net (code "151") (name "unconnected-(J2-Pad17)") (class "Default")
      (node (ref "J2") (pin "17") (pintype "bidirectional"))
    )
    (net (code "152") (name "unconnected-(J2-Pad19)") (class "Default")
      (node (ref "J2") (pin "19") (pintype "bidirectional"))
    )
    (net (code "153") (name "unconnected-(J2-Pad21)") (class "Default")
      (node (ref "J2") (pin "21") (pintype "bidirectional"))
    )
    (net (code "154") (name "unconnected-(J2-Pad29)") (class "Default")
      (node (ref "J2") (pin "29") (pintype "bidirectional"))
    )
    (net (code "155") (name "unconnected-(J2-Pad30)") (class "Default")
      (node (ref "J2") (pin "30") (pintype "bidirectional"))
    )
    (net (code "156") (name "unconnected-(J2-Pad31)") (class "Default")
      (node (ref "J2") (pin "31") (pintype "bidirectional"))
    )
    (net (code "157") (name "unconnected-(J2-Pad32)") (class "Default")
      (node (ref "J2") (pin "32") (pintype "bidirectional"))
    )
    (net (code "158") (name "unconnected-(J2-Pad35)") (class "Default")
      (node (ref "J2") (pin "35") (pintype "bidirectional"))
    )
    (net (code "159") (name "unconnected-(J2-Pad37)") (class "Default")
      (node (ref "J2") (pin "37") (pintype "bidirectional"))
    )
    (net (code "160") (name "unconnected-(J2-Pad39)") (class "Default")
      (node (ref "J2") (pin "39") (pintype "bidirectional"))
    )
    (net (code "161") (name "unconnected-(J2-Pad41)") (class "Default")
      (node (ref "J2") (pin "41") (pintype "bidirectional"))
    )
    (net (code "162") (name "unconnected-(J2-Pad55)") (class "Default")
      (node (ref "J2") (pin "55") (pintype "bidirectional"))
    )
    (net (code "163") (name "unconnected-(J2-PadMP1)") (class "Default")
      (node (ref "J2") (pin "MP1") (pinfunction "MP1_MP1") (pintype "bidirectional"))
    )
    (net (code "164") (name "unconnected-(J2-PadMP2)") (class "Default")
      (node (ref "J2") (pin "MP2") (pinfunction "MP2_MP2") (pintype "bidirectional"))
    )
    (net (code "165") (name "unconnected-(J2-PadMP3)") (class "Default")
      (node (ref "J2") (pin "MP3") (pinfunction "MP3_MP3") (pintype "bidirectional"))
    )
    (net (code "166") (name "unconnected-(J2-PadMP4)") (class "Default")
      (node (ref "J2") (pin "MP4") (pinfunction "MP4_MP4") (pintype "bidirectional"))
    )
    (net (code "167") (name "unconnected-(J2-VCC-Pad34)") (class "Default")
      (node (ref "J2") (pin "34") (pinfunction "VCC_34") (pintype "bidirectional"))
    )
    (net (code "168") (name "unconnected-(U1-Pad5V)") (class "Default")
      (node (ref "U1") (pin "5V") (pinfunction "5V_5V") (pintype "unspecified"))
    )
  )
)
